# L.net
KiCad netlist of a schematic drawn in EAGLE
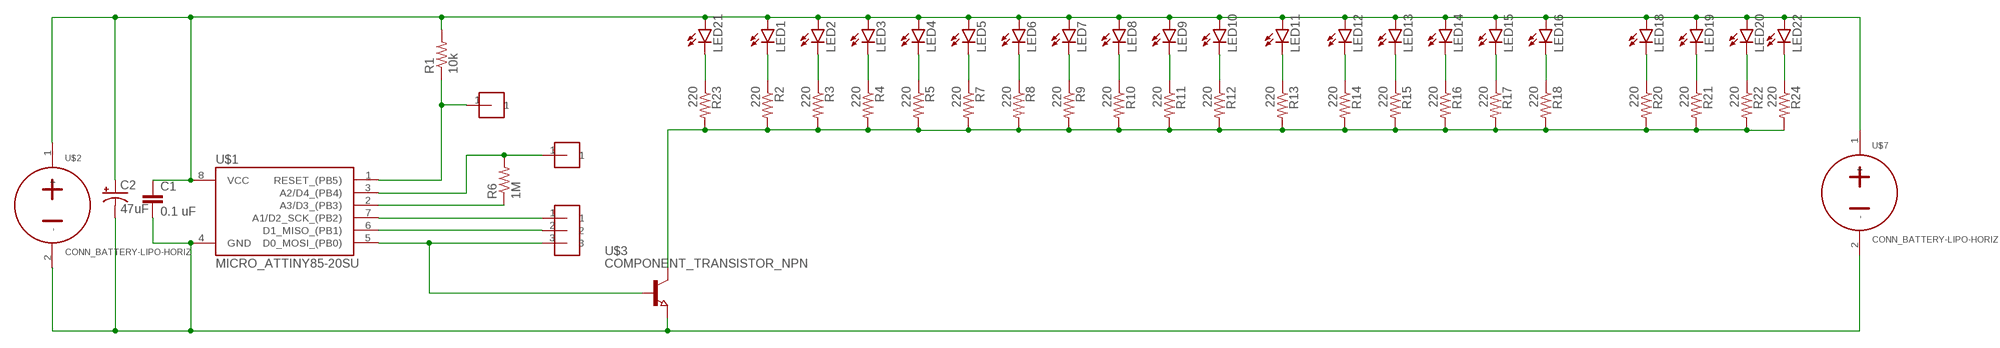
[diagram p0: schematic, sheet 1]

(export (version "E")
  (design (tool "Eeschema 10.0.6"))
  (components
    (comp (ref "C1")
      (value "0.1 uF")
      (footprint "eagle-import:0805")
      (libsource (lib "eagle-import") (part "COMPONENT_CAP-0805"))
    )
    (comp (ref "C2")
      (value "47uF")
      (footprint "eagle-import:CAP_RADIAL_CAN_10MM")
      (libsource (lib "eagle-import") (part "COMPONENT_CAP_POL-6.3MM"))
    )
    (comp (ref "LED1")
      (value "LED-0805")
      (footprint "eagle-import:CHIP-LED0805")
      (libsource (lib "eagle-import") (part "LED-0805"))
    )
    (comp (ref "LED2")
      (value "LED-0805")
      (footprint "eagle-import:CHIP-LED0805")
      (libsource (lib "eagle-import") (part "LED-0805"))
    )
    (comp (ref "LED3")
      (value "LED-0805")
      (footprint "eagle-import:CHIP-LED0805")
      (libsource (lib "eagle-import") (part "LED-0805"))
    )
    (comp (ref "LED4")
      (value "LED-0805")
      (footprint "eagle-import:CHIP-LED0805")
      (libsource (lib "eagle-import") (part "LED-0805"))
    )
    (comp (ref "LED5")
      (value "LED-0805")
      (footprint "eagle-import:CHIP-LED0805")
      (libsource (lib "eagle-import") (part "LED-0805"))
    )
    (comp (ref "LED6")
      (value "LED-0805")
      (footprint "eagle-import:CHIP-LED0805")
      (libsource (lib "eagle-import") (part "LED-0805"))
    )
    (comp (ref "LED7")
      (value "LED-0805")
      (footprint "eagle-import:CHIP-LED0805")
      (libsource (lib "eagle-import") (part "LED-0805"))
    )
    (comp (ref "LED8")
      (value "LED-0805")
      (footprint "eagle-import:CHIP-LED0805")
      (libsource (lib "eagle-import") (part "LED-0805"))
    )
    (comp (ref "LED9")
      (value "LED-0805")
      (footprint "eagle-import:CHIP-LED0805")
      (libsource (lib "eagle-import") (part "LED-0805"))
    )
    (comp (ref "LED10")
      (value "LED-0805")
      (footprint "eagle-import:CHIP-LED0805")
      (libsource (lib "eagle-import") (part "LED-0805"))
    )
    (comp (ref "LED11")
      (value "LED-0805")
      (footprint "eagle-import:CHIP-LED0805")
      (libsource (lib "eagle-import") (part "LED-0805"))
    )
    (comp (ref "LED12")
      (value "LED-0805")
      (footprint "eagle-import:CHIP-LED0805")
      (libsource (lib "eagle-import") (part "LED-0805"))
    )
    (comp (ref "LED13")
      (value "LED-0805")
      (footprint "eagle-import:CHIP-LED0805")
      (libsource (lib "eagle-import") (part "LED-0805"))
    )
    (comp (ref "LED14")
      (value "LED-0805")
      (footprint "eagle-import:CHIP-LED0805")
      (libsource (lib "eagle-import") (part "LED-0805"))
    )
    (comp (ref "LED15")
      (value "LED-0805")
      (footprint "eagle-import:CHIP-LED0805")
      (libsource (lib "eagle-import") (part "LED-0805"))
    )
    (comp (ref "LED16")
      (value "LED-0805")
      (footprint "eagle-import:CHIP-LED0805")
      (libsource (lib "eagle-import") (part "LED-0805"))
    )
    (comp (ref "LED18")
      (value "LED-0805")
      (footprint "eagle-import:CHIP-LED0805")
      (libsource (lib "eagle-import") (part "LED-0805"))
    )
    (comp (ref "LED19")
      (value "LED-0805")
      (footprint "eagle-import:CHIP-LED0805")
      (libsource (lib "eagle-import") (part "LED-0805"))
    )
    (comp (ref "LED20")
      (value "LED-0805")
      (footprint "eagle-import:CHIP-LED0805")
      (libsource (lib "eagle-import") (part "LED-0805"))
    )
    (comp (ref "LED21")
      (value "LED-0805")
      (footprint "eagle-import:CHIP-LED0805")
      (libsource (lib "eagle-import") (part "LED-0805"))
    )
    (comp (ref "LED22")
      (value "LED-0805")
      (footprint "eagle-import:CHIP-LED0805")
      (libsource (lib "eagle-import") (part "LED-0805"))
    )
    (comp (ref "R1")
      (value "10k")
      (footprint "eagle-import:0805")
      (libsource (lib "eagle-import") (part "COMPONENT_RESISTOR-0805"))
    )
    (comp (ref "R2")
      (value "220")
      (footprint "eagle-import:0805")
      (libsource (lib "eagle-import") (part "COMPONENT_RESISTOR-0805"))
    )
    (comp (ref "R3")
      (value "220")
      (footprint "eagle-import:0805")
      (libsource (lib "eagle-import") (part "COMPONENT_RESISTOR-0805"))
    )
    (comp (ref "R4")
      (value "220")
      (footprint "eagle-import:0805")
      (libsource (lib "eagle-import") (part "COMPONENT_RESISTOR-0805"))
    )
    (comp (ref "R5")
      (value "220")
      (footprint "eagle-import:0805")
      (libsource (lib "eagle-import") (part "COMPONENT_RESISTOR-0805"))
    )
    (comp (ref "R6")
      (value "1M")
      (footprint "eagle-import:0805")
      (libsource (lib "eagle-import") (part "COMPONENT_RESISTOR-0805"))
    )
    (comp (ref "R7")
      (value "220")
      (footprint "eagle-import:0805")
      (libsource (lib "eagle-import") (part "COMPONENT_RESISTOR-0805"))
    )
    (comp (ref "R8")
      (value "220")
      (footprint "eagle-import:0805")
      (libsource (lib "eagle-import") (part "COMPONENT_RESISTOR-0805"))
    )
    (comp (ref "R9")
      (value "220")
      (footprint "eagle-import:0805")
      (libsource (lib "eagle-import") (part "COMPONENT_RESISTOR-0805"))
    )
    (comp (ref "R10")
      (value "220")
      (footprint "eagle-import:0805")
      (libsource (lib "eagle-import") (part "COMPONENT_RESISTOR-0805"))
    )
    (comp (ref "R11")
      (value "220")
      (footprint "eagle-import:0805")
      (libsource (lib "eagle-import") (part "COMPONENT_RESISTOR-0805"))
    )
    (comp (ref "R12")
      (value "220")
      (footprint "eagle-import:0805")
      (libsource (lib "eagle-import") (part "COMPONENT_RESISTOR-0805"))
    )
    (comp (ref "R13")
      (value "220")
      (footprint "eagle-import:0805")
      (libsource (lib "eagle-import") (part "COMPONENT_RESISTOR-0805"))
    )
    (comp (ref "R14")
      (value "220")
      (footprint "eagle-import:0805")
      (libsource (lib "eagle-import") (part "COMPONENT_RESISTOR-0805"))
    )
    (comp (ref "R15")
      (value "220")
      (footprint "eagle-import:0805")
      (libsource (lib "eagle-import") (part "COMPONENT_RESISTOR-0805"))
    )
    (comp (ref "R16")
      (value "220")
      (footprint "eagle-import:0805")
      (libsource (lib "eagle-import") (part "COMPONENT_RESISTOR-0805"))
    )
    (comp (ref "R17")
      (value "220")
      (footprint "eagle-import:0805")
      (libsource (lib "eagle-import") (part "COMPONENT_RESISTOR-0805"))
    )
    (comp (ref "R18")
      (value "220")
      (footprint "eagle-import:0805")
      (libsource (lib "eagle-import") (part "COMPONENT_RESISTOR-0805"))
    )
    (comp (ref "R20")
      (value "220")
      (footprint "eagle-import:0805")
      (libsource (lib "eagle-import") (part "COMPONENT_RESISTOR-0805"))
    )
    (comp (ref "R21")
      (value "220")
      (footprint "eagle-import:0805")
      (libsource (lib "eagle-import") (part "COMPONENT_RESISTOR-0805"))
    )
    (comp (ref "R22")
      (value "220")
      (footprint "eagle-import:0805")
      (libsource (lib "eagle-import") (part "COMPONENT_RESISTOR-0805"))
    )
    (comp (ref "R23")
      (value "220")
      (footprint "eagle-import:0805")
      (libsource (lib "eagle-import") (part "COMPONENT_RESISTOR-0805"))
    )
    (comp (ref "R24")
      (value "220")
      (footprint "eagle-import:0805")
      (libsource (lib "eagle-import") (part "COMPONENT_RESISTOR-0805"))
    )
    (comp (ref "U$1")
      (value "MICRO_ATTINY85-20SU")
      (footprint "eagle-import:SOIC8")
      (libsource (lib "eagle-import") (part "MICRO_ATTINY85-20SU"))
    )
    (comp (ref "U$2")
      (value "CONN_BATTERY-LIPO-HORIZ")
      (footprint "eagle-import:JST-PH-2-SMT-RA")
      (libsource (lib "eagle-import") (part "CONN_BATTERY-LIPO-HORIZ"))
    )
    (comp (ref "U$3")
      (value "COMPONENT_TRANSISTOR_NPN")
      (footprint "eagle-import:SOT23")
      (libsource (lib "eagle-import") (part "COMPONENT_TRANSISTOR_NPN"))
    )
    (comp (ref "U$4")
      (value "HEADER-1-TESTPOINT")
      (footprint "eagle-import:TESTPOINT-1")
      (libsource (lib "eagle-import") (part "HEADER-1-TESTPOINT"))
    )
    (comp (ref "U$5")
      (value "HEADER-1-TESTPOINT")
      (footprint "eagle-import:TESTPOINT-1")
      (libsource (lib "eagle-import") (part "HEADER-1-TESTPOINT"))
    )
    (comp (ref "U$6")
      (value "HEADER-3-TESTPOINT")
      (footprint "eagle-import:TESTPOINT-3")
      (libsource (lib "eagle-import") (part "HEADER-3-TESTPOINT"))
    )
    (comp (ref "U$7")
      (value "CONN_BATTERY-LIPO-HORIZ")
      (footprint "eagle-import:JST-PH-2-SMT-RA")
      (libsource (lib "eagle-import") (part "CONN_BATTERY-LIPO-HORIZ"))
    )
  )
  (nets
    (net (code "1") (name "Net-(LED1-PadC)") (class "Default")
      (node (ref "LED1") (pin "C") (pinfunction "C_C") (pintype "passive"))
      (node (ref "R2") (pin "1") (pinfunction "1_1") (pintype "passive"))
    )
    (net (code "2") (name "Net-(LED2-PadC)") (class "Default")
      (node (ref "LED2") (pin "C") (pinfunction "C_C") (pintype "passive"))
      (node (ref "R3") (pin "1") (pinfunction "1_1") (pintype "passive"))
    )
    (net (code "3") (name "Net-(LED3-PadC)") (class "Default")
      (node (ref "LED3") (pin "C") (pinfunction "C_C") (pintype "passive"))
      (node (ref "R4") (pin "1") (pinfunction "1_1") (pintype "passive"))
    )
    (net (code "4") (name "Net-(LED4-PadC)") (class "Default")
      (node (ref "LED4") (pin "C") (pinfunction "C_C") (pintype "passive"))
      (node (ref "R5") (pin "1") (pinfunction "1_1") (pintype "passive"))
    )
    (net (code "5") (name "Net-(LED5-PadC)") (class "Default")
      (node (ref "LED5") (pin "C") (pinfunction "C_C") (pintype "passive"))
      (node (ref "R7") (pin "1") (pinfunction "1_1") (pintype "passive"))
    )
    (net (code "6") (name "Net-(LED6-PadC)") (class "Default")
      (node (ref "LED6") (pin "C") (pinfunction "C_C") (pintype "passive"))
      (node (ref "R8") (pin "1") (pinfunction "1_1") (pintype "passive"))
    )
    (net (code "7") (name "Net-(LED7-PadC)") (class "Default")
      (node (ref "LED7") (pin "C") (pinfunction "C_C") (pintype "passive"))
      (node (ref "R9") (pin "1") (pinfunction "1_1") (pintype "passive"))
    )
    (net (code "8") (name "Net-(LED8-PadC)") (class "Default")
      (node (ref "LED8") (pin "C") (pinfunction "C_C") (pintype "passive"))
      (node (ref "R10") (pin "1") (pinfunction "1_1") (pintype "passive"))
    )
    (net (code "9") (name "Net-(LED9-PadC)") (class "Default")
      (node (ref "LED9") (pin "C") (pinfunction "C_C") (pintype "passive"))
      (node (ref "R11") (pin "1") (pinfunction "1_1") (pintype "passive"))
    )
    (net (code "10") (name "Net-(LED10-PadC)") (class "Default")
      (node (ref "LED10") (pin "C") (pinfunction "C_C") (pintype "passive"))
      (node (ref "R12") (pin "1") (pinfunction "1_1") (pintype "passive"))
    )
    (net (code "11") (name "Net-(LED11-PadC)") (class "Default")
      (node (ref "LED11") (pin "C") (pinfunction "C_C") (pintype "passive"))
      (node (ref "R13") (pin "1") (pinfunction "1_1") (pintype "passive"))
    )
    (net (code "12") (name "Net-(LED12-PadC)") (class "Default")
      (node (ref "LED12") (pin "C") (pinfunction "C_C") (pintype "passive"))
      (node (ref "R14") (pin "1") (pinfunction "1_1") (pintype "passive"))
    )
    (net (code "13") (name "Net-(LED13-PadC)") (class "Default")
      (node (ref "LED13") (pin "C") (pinfunction "C_C") (pintype "passive"))
      (node (ref "R15") (pin "1") (pinfunction "1_1") (pintype "passive"))
    )
    (net (code "14") (name "Net-(LED14-PadC)") (class "Default")
      (node (ref "LED14") (pin "C") (pinfunction "C_C") (pintype "passive"))
      (node (ref "R16") (pin "1") (pinfunction "1_1") (pintype "passive"))
    )
    (net (code "15") (name "Net-(LED15-PadC)") (class "Default")
      (node (ref "LED15") (pin "C") (pinfunction "C_C") (pintype "passive"))
      (node (ref "R17") (pin "1") (pinfunction "1_1") (pintype "passive"))
    )
    (net (code "16") (name "Net-(LED16-PadC)") (class "Default")
      (node (ref "LED16") (pin "C") (pinfunction "C_C") (pintype "passive"))
      (node (ref "R18") (pin "1") (pinfunction "1_1") (pintype "passive"))
    )
    (net (code "17") (name "Net-(LED18-PadC)") (class "Default")
      (node (ref "LED18") (pin "C") (pinfunction "C_C") (pintype "passive"))
      (node (ref "R20") (pin "1") (pinfunction "1_1") (pintype "passive"))
    )
    (net (code "18") (name "Net-(LED19-PadC)") (class "Default")
      (node (ref "LED19") (pin "C") (pinfunction "C_C") (pintype "passive"))
      (node (ref "R21") (pin "1") (pinfunction "1_1") (pintype "passive"))
    )
    (net (code "19") (name "Net-(LED20-PadC)") (class "Default")
      (node (ref "LED20") (pin "C") (pinfunction "C_C") (pintype "passive"))
      (node (ref "R22") (pin "1") (pinfunction "1_1") (pintype "passive"))
    )
    (net (code "20") (name "Net-(LED21-PadC)") (class "Default")
      (node (ref "LED21") (pin "C") (pinfunction "C_C") (pintype "passive"))
      (node (ref "R23") (pin "1") (pinfunction "1_1") (pintype "passive"))
    )
    (net (code "21") (name "Net-(LED22-PadC)") (class "Default")
      (node (ref "LED22") (pin "C") (pinfunction "C_C") (pintype "passive"))
      (node (ref "R24") (pin "1") (pinfunction "1_1") (pintype "passive"))
    )
    (net (code "22") (name "Net-(U$1-A1{slash}D2_SCK_(PB2))") (class "Default")
      (node (ref "U$1") (pin "7") (pinfunction "A1/D2_SCK_(PB2)_7") (pintype "bidirectional"))
      (node (ref "U$6") (pin "1") (pinfunction "1_1") (pintype "bidirectional"))
    )
    (net (code "23") (name "Net-(U$1-A2{slash}D4_(PB4))") (class "Default")
      (node (ref "R6") (pin "2") (pinfunction "2_2") (pintype "passive"))
      (node (ref "U$1") (pin "3") (pinfunction "A2/D4_(PB4)_3") (pintype "bidirectional"))
      (node (ref "U$4") (pin "1") (pinfunction "1_1") (pintype "bidirectional"))
    )
    (net (code "24") (name "Net-(U$1-A3{slash}D3_(PB3))") (class "Default")
      (node (ref "R6") (pin "1") (pinfunction "1_1") (pintype "passive"))
      (node (ref "U$1") (pin "2") (pinfunction "A3/D3_(PB3)_2") (pintype "bidirectional"))
    )
    (net (code "25") (name "Net-(U$1-D0_MOSI_(PB0))") (class "Default")
      (node (ref "U$1") (pin "5") (pinfunction "D0_MOSI_(PB0)_5") (pintype "bidirectional"))
      (node (ref "U$3") (pin "1") (pinfunction "B_1") (pintype "passive"))
      (node (ref "U$6") (pin "3") (pinfunction "3_3") (pintype "bidirectional"))
    )
    (net (code "26") (name "Net-(U$1-D1_MISO_(PB1))") (class "Default")
      (node (ref "U$1") (pin "6") (pinfunction "D1_MISO_(PB1)_6") (pintype "bidirectional"))
      (node (ref "U$6") (pin "2") (pinfunction "2_2") (pintype "bidirectional"))
    )
    (net (code "27") (name "Net-(U$1-GND)") (class "Default")
      (node (ref "C1") (pin "2") (pinfunction "2_2") (pintype "passive"))
      (node (ref "C2") (pin "-") (pinfunction "-_-") (pintype "passive"))
      (node (ref "U$1") (pin "4") (pinfunction "GND_4") (pintype "power_in"))
      (node (ref "U$2") (pin "2") (pinfunction "-_2") (pintype "bidirectional"))
      (node (ref "U$3") (pin "2") (pinfunction "E_2") (pintype "passive"))
      (node (ref "U$7") (pin "2") (pinfunction "-_2") (pintype "bidirectional"))
    )
    (net (code "28") (name "Net-(U$1-RESET_(PB5))") (class "Default")
      (node (ref "R1") (pin "1") (pinfunction "1_1") (pintype "passive"))
      (node (ref "U$1") (pin "1") (pinfunction "RESET_(PB5)_1") (pintype "bidirectional"))
      (node (ref "U$5") (pin "1") (pinfunction "1_1") (pintype "bidirectional"))
    )
    (net (code "29") (name "Net-(U$1-VCC)") (class "Default")
      (node (ref "C1") (pin "1") (pinfunction "1_1") (pintype "passive"))
      (node (ref "C2") (pin "+") (pinfunction "+_+") (pintype "passive"))
      (node (ref "LED1") (pin "A") (pinfunction "A_A") (pintype "passive"))
      (node (ref "LED10") (pin "A") (pinfunction "A_A") (pintype "passive"))
      (node (ref "LED11") (pin "A") (pinfunction "A_A") (pintype "passive"))
      (node (ref "LED12") (pin "A") (pinfunction "A_A") (pintype "passive"))
      (node (ref "LED13") (pin "A") (pinfunction "A_A") (pintype "passive"))
      (node (ref "LED14") (pin "A") (pinfunction "A_A") (pintype "passive"))
      (node (ref "LED15") (pin "A") (pinfunction "A_A") (pintype "passive"))
      (node (ref "LED16") (pin "A") (pinfunction "A_A") (pintype "passive"))
      (node (ref "LED18") (pin "A") (pinfunction "A_A") (pintype "passive"))
      (node (ref "LED19") (pin "A") (pinfunction "A_A") (pintype "passive"))
      (node (ref "LED2") (pin "A") (pinfunction "A_A") (pintype "passive"))
      (node (ref "LED20") (pin "A") (pinfunction "A_A") (pintype "passive"))
      (node (ref "LED21") (pin "A") (pinfunction "A_A") (pintype "passive"))
      (node (ref "LED22") (pin "A") (pinfunction "A_A") (pintype "passive"))
      (node (ref "LED3") (pin "A") (pinfunction "A_A") (pintype "passive"))
      (node (ref "LED4") (pin "A") (pinfunction "A_A") (pintype "passive"))
      (node (ref "LED5") (pin "A") (pinfunction "A_A") (pintype "passive"))
      (node (ref "LED6") (pin "A") (pinfunction "A_A") (pintype "passive"))
      (node (ref "LED7") (pin "A") (pinfunction "A_A") (pintype "passive"))
      (node (ref "LED8") (pin "A") (pinfunction "A_A") (pintype "passive"))
      (node (ref "LED9") (pin "A") (pinfunction "A_A") (pintype "passive"))
      (node (ref "R1") (pin "2") (pinfunction "2_2") (pintype "passive"))
      (node (ref "U$1") (pin "8") (pinfunction "VCC_8") (pintype "power_in"))
      (node (ref "U$2") (pin "1") (pinfunction "+_1") (pintype "bidirectional"))
      (node (ref "U$7") (pin "1") (pinfunction "+_1") (pintype "bidirectional"))
    )
    (net (code "30") (name "Net-(U$3-C)") (class "Default")
      (node (ref "R10") (pin "2") (pinfunction "2_2") (pintype "passive"))
      (node (ref "R11") (pin "2") (pinfunction "2_2") (pintype "passive"))
      (node (ref "R12") (pin "2") (pinfunction "2_2") (pintype "passive"))
      (node (ref "R13") (pin "2") (pinfunction "2_2") (pintype "passive"))
      (node (ref "R14") (pin "2") (pinfunction "2_2") (pintype "passive"))
      (node (ref "R15") (pin "2") (pinfunction "2_2") (pintype "passive"))
      (node (ref "R16") (pin "2") (pinfunction "2_2") (pintype "passive"))
      (node (ref "R17") (pin "2") (pinfunction "2_2") (pintype "passive"))
      (node (ref "R18") (pin "2") (pinfunction "2_2") (pintype "passive"))
      (node (ref "R2") (pin "2") (pinfunction "2_2") (pintype "passive"))
      (node (ref "R20") (pin "2") (pinfunction "2_2") (pintype "passive"))
      (node (ref "R21") (pin "2") (pinfunction "2_2") (pintype "passive"))
      (node (ref "R22") (pin "2") (pinfunction "2_2") (pintype "passive"))
      (node (ref "R23") (pin "2") (pinfunction "2_2") (pintype "passive"))
      (node (ref "R24") (pin "2") (pinfunction "2_2") (pintype "passive"))
      (node (ref "R3") (pin "2") (pinfunction "2_2") (pintype "passive"))
      (node (ref "R4") (pin "2") (pinfunction "2_2") (pintype "passive"))
      (node (ref "R5") (pin "2") (pinfunction "2_2") (pintype "passive"))
      (node (ref "R7") (pin "2") (pinfunction "2_2") (pintype "passive"))
      (node (ref "R8") (pin "2") (pinfunction "2_2") (pintype "passive"))
      (node (ref "R9") (pin "2") (pinfunction "2_2") (pintype "passive"))
      (node (ref "U$3") (pin "3") (pinfunction "C_3") (pintype "passive"))
    )
  )
)
